# ESP32.net
KiCad netlist of a schematic drawn in Altium Designer
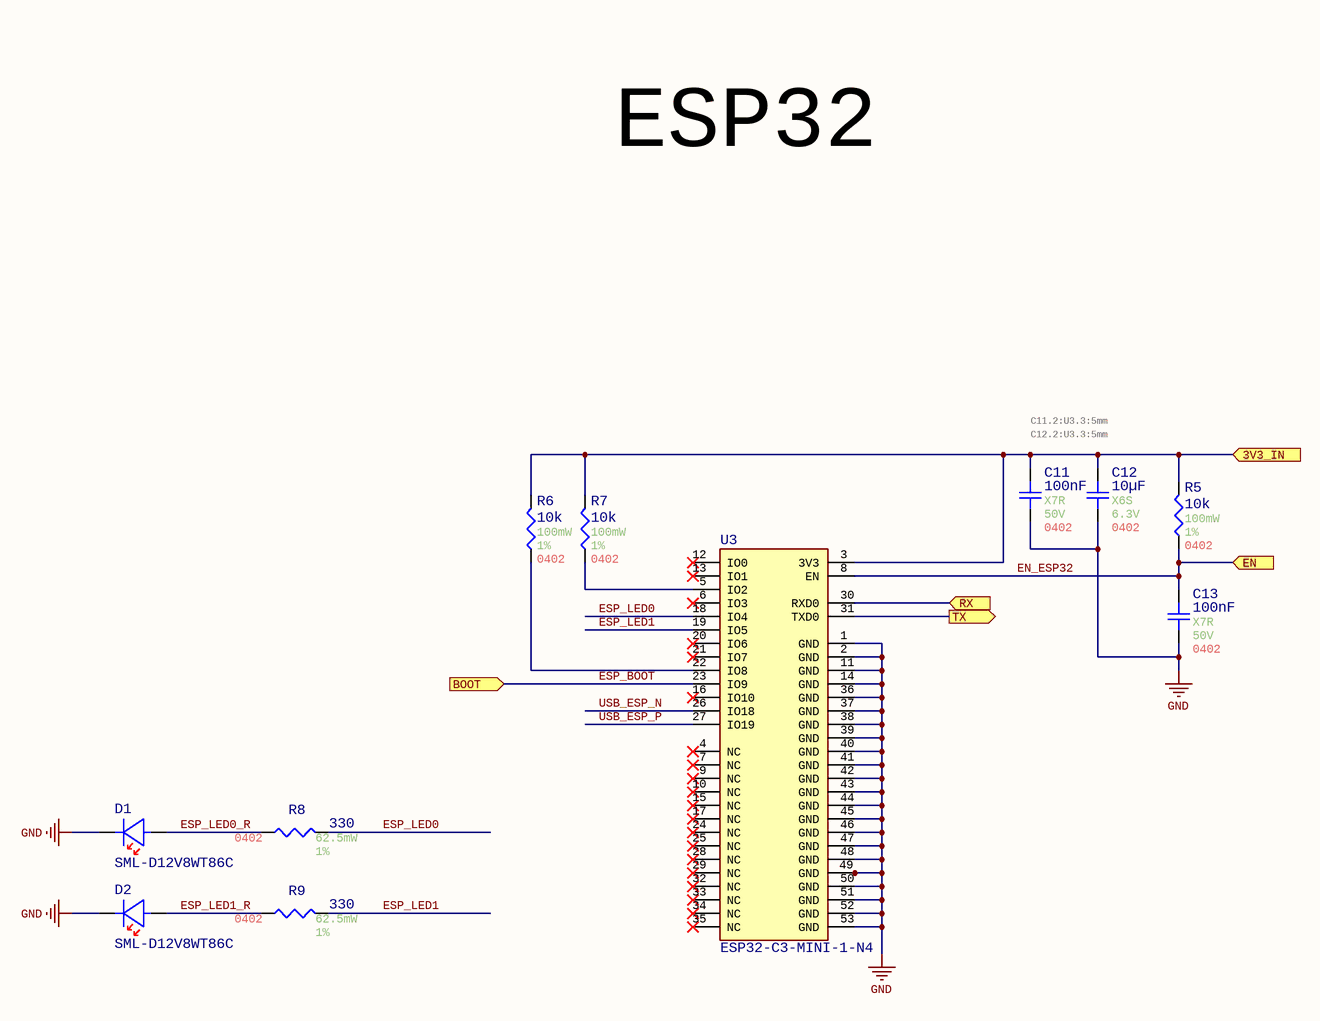
[diagram p0: ESP32.SchDoc]

(export (version "E")
  (design (tool "Eeschema 10.0.6"))
  (components
    (comp (ref "C11")
      (value "100nF")
      (footprint "Generic 0402 capacitor")
      (fields
        (field (name "TEMPERATURE COEFFICIENT") "X7R")
        (field (name "VOLTAGE RATING") "50V")
        (field (name "CASE/PACKAGE") "0402")
        (field (name "TOLERANCE") "10%")
        (field (name "PLACENEAR") "C11.2:U3.3:5mm")
        (field (name "Comment") "GRT155R71H104KE01D")
      )
      (libsource (lib "Raise Robotics") (part "Unpolarized Capacitor"))
    )
    (comp (ref "C12")
      (value "10µF")
      (footprint "Generic 0402 capacitor")
      (description "Multilayer Ceramic Capacitors MLCC - SMD/SMT 0402 10uF 6.3VDC 20% X6S AEC-Q200")
      (fields
        (field (name "TEMPERATURE COEFFICIENT") "X6S")
        (field (name "VOLTAGE RATING") "6.3V")
        (field (name "CASE/PACKAGE") "0402")
        (field (name "TOLERANCE") "20%")
        (field (name "PLACENEAR") "C12.2:U3.3:5mm")
        (field (name "Comment") "GRT155C80J106ME13J")
      )
      (libsource (lib "Raise Robotics") (part "Unpolarized Capacitor"))
    )
    (comp (ref "C13")
      (value "100nF")
      (footprint "Generic 0402 capacitor")
      (fields
        (field (name "TEMPERATURE COEFFICIENT") "X7R")
        (field (name "VOLTAGE RATING") "50V")
        (field (name "CASE/PACKAGE") "0402")
        (field (name "TOLERANCE") "10%")
        (field (name "Comment") "GRT155R71H104KE01D")
      )
      (libsource (lib "Raise Robotics") (part "Unpolarized Capacitor"))
    )
    (comp (ref "D1")
      (value "SML-D12V8WT86C")
      (footprint "FP-SML-D12-MFG")
      (description "Red 630nm LED Indication - Discrete 2.2V 0603 (1608 Metric)")
      (libsource (lib "Raise Robotics") (part "LED Red"))
    )
    (comp (ref "D2")
      (value "SML-D12V8WT86C")
      (footprint "FP-SML-D12-MFG")
      (description "Red 630nm LED Indication - Discrete 2.2V 0603 (1608 Metric)")
      (libsource (lib "Raise Robotics") (part "LED Red"))
    )
    (comp (ref "R5")
      (value "10k")
      (footprint "Generic 0402 Resistor")
      (description "Fixed Resistor, Thin Film, 0.1W, 10000ohm, 50V, 1% +/-Tol, 100ppm/Cel, Surface Mount, 0402")
      (fields
        (field (name "POWER") "100mW")
        (field (name "TOLERANCE") "1%")
        (field (name "CASE/PACKAGE") "0402")
        (field (name "MANUFACTURER PART NUMBER") "Blank")
        (field (name "Comment") "RNCP0402FTD10K0")
      )
      (libsource (lib "Raise Robotics") (part "Resistor"))
    )
    (comp (ref "R6")
      (value "10k")
      (footprint "Generic 0402 Resistor")
      (description "Fixed Resistor, Thin Film, 0.1W, 10000ohm, 50V, 1% +/-Tol, 100ppm/Cel, Surface Mount, 0402")
      (fields
        (field (name "POWER") "100mW")
        (field (name "TOLERANCE") "1%")
        (field (name "CASE/PACKAGE") "0402")
        (field (name "MANUFACTURER PART NUMBER") "Blank")
        (field (name "Comment") "RNCP0402FTD10K0")
      )
      (libsource (lib "Raise Robotics") (part "Resistor"))
    )
    (comp (ref "R7")
      (value "10k")
      (footprint "Generic 0402 Resistor")
      (description "Fixed Resistor, Thin Film, 0.1W, 10000ohm, 50V, 1% +/-Tol, 100ppm/Cel, Surface Mount, 0402")
      (fields
        (field (name "POWER") "100mW")
        (field (name "TOLERANCE") "1%")
        (field (name "CASE/PACKAGE") "0402")
        (field (name "MANUFACTURER PART NUMBER") "Blank")
        (field (name "Comment") "RNCP0402FTD10K0")
      )
      (libsource (lib "Raise Robotics") (part "Resistor"))
    )
    (comp (ref "R8")
      (value "330")
      (footprint "Generic 0402 Resistor")
      (description "Res Thick Film 0402 330 Ohm 1% 0.063W ±100ppm/°C Molded SMD Paper T/R")
      (fields
        (field (name "POWER") "62.5mW")
        (field (name "TOLERANCE") "1%")
        (field (name "CASE/PACKAGE") "0402")
        (field (name "Comment") "RMCF0402FT330R")
      )
      (libsource (lib "Raise Robotics") (part "Resistor"))
    )
    (comp (ref "R9")
      (value "330")
      (footprint "Generic 0402 Resistor")
      (description "Res Thick Film 0402 330 Ohm 1% 0.063W ±100ppm/°C Molded SMD Paper T/R")
      (fields
        (field (name "POWER") "62.5mW")
        (field (name "TOLERANCE") "1%")
        (field (name "CASE/PACKAGE") "0402")
        (field (name "Comment") "RMCF0402FT330R")
      )
      (libsource (lib "Raise Robotics") (part "Resistor"))
    )
    (comp (ref "U3")
      (value "ESP32-C3-MINI-1-N4")
      (footprint "ESP32-C3-MINI-1-N4")
      (libsource (lib "Raise Robotics") (part "ESP32-C3-MINI-1"))
    )
  )
  (nets
    (net (code "1") (name "/3V3_IN") (class "Default")
      (node (ref "C11") (pin "2") (pinfunction "2_2") (pintype "passive"))
      (node (ref "C12") (pin "2") (pinfunction "2_2") (pintype "passive"))
      (node (ref "R5") (pin "2") (pinfunction "2_2") (pintype "passive"))
      (node (ref "R6") (pin "2") (pinfunction "2_2") (pintype "passive"))
      (node (ref "R7") (pin "2") (pinfunction "2_2") (pintype "passive"))
      (node (ref "U3") (pin "3") (pinfunction "3V3_3") (pintype "passive"))
    )
    (net (code "2") (name "/EN_ESP32") (class "Default")
      (node (ref "C13") (pin "2") (pinfunction "2_2") (pintype "passive"))
      (node (ref "R5") (pin "1") (pinfunction "1_1") (pintype "passive"))
      (node (ref "U3") (pin "8") (pinfunction "EN_8") (pintype "passive"))
    )
    (net (code "3") (name "/ESP_BOOT") (class "Default")
      (node (ref "U3") (pin "23") (pinfunction "IO9_23") (pintype "passive"))
    )
    (net (code "4") (name "/ESP_LED0") (class "Default")
      (node (ref "R8") (pin "2") (pinfunction "2_2") (pintype "passive"))
      (node (ref "U3") (pin "18") (pinfunction "IO4_18") (pintype "passive"))
    )
    (net (code "5") (name "/ESP_LED0_R") (class "Default")
      (node (ref "D1") (pin "2") (pinfunction "A_2") (pintype "passive"))
      (node (ref "R8") (pin "1") (pinfunction "1_1") (pintype "passive"))
    )
    (net (code "6") (name "/ESP_LED1") (class "Default")
      (node (ref "R9") (pin "2") (pinfunction "2_2") (pintype "passive"))
      (node (ref "U3") (pin "19") (pinfunction "IO5_19") (pintype "passive"))
    )
    (net (code "7") (name "/ESP_LED1_R") (class "Default")
      (node (ref "D2") (pin "2") (pinfunction "A_2") (pintype "passive"))
      (node (ref "R9") (pin "1") (pinfunction "1_1") (pintype "passive"))
    )
    (net (code "8") (name "/RX") (class "Default")
      (node (ref "U3") (pin "30") (pinfunction "RXD0_30") (pintype "passive"))
    )
    (net (code "9") (name "/TX") (class "Default")
      (node (ref "U3") (pin "31") (pinfunction "TXD0_31") (pintype "passive"))
    )
    (net (code "10") (name "/USB_ESP_N") (class "Default")
      (node (ref "U3") (pin "26") (pinfunction "IO18_26") (pintype "passive"))
    )
    (net (code "11") (name "/USB_ESP_P") (class "Default")
      (node (ref "U3") (pin "27") (pinfunction "IO19_27") (pintype "passive"))
    )
    (net (code "12") (name "GND") (class "Default")
      (node (ref "C11") (pin "1") (pinfunction "1_1") (pintype "passive"))
      (node (ref "C12") (pin "1") (pinfunction "1_1") (pintype "passive"))
      (node (ref "C13") (pin "1") (pinfunction "1_1") (pintype "passive"))
      (node (ref "D1") (pin "1") (pinfunction "C_1") (pintype "passive"))
      (node (ref "D2") (pin "1") (pinfunction "C_1") (pintype "passive"))
      (node (ref "U3") (pin "1") (pinfunction "GND_1") (pintype "passive"))
      (node (ref "U3") (pin "11") (pinfunction "GND_11") (pintype "passive"))
      (node (ref "U3") (pin "14") (pinfunction "GND_14") (pintype "passive"))
      (node (ref "U3") (pin "2") (pinfunction "GND_2") (pintype "passive"))
      (node (ref "U3") (pin "36") (pinfunction "GND_36") (pintype "passive"))
      (node (ref "U3") (pin "37") (pinfunction "GND_37") (pintype "passive"))
      (node (ref "U3") (pin "38") (pinfunction "GND_38") (pintype "passive"))
      (node (ref "U3") (pin "39") (pinfunction "GND_39") (pintype "passive"))
      (node (ref "U3") (pin "40") (pinfunction "GND_40") (pintype "passive"))
      (node (ref "U3") (pin "41") (pinfunction "GND_41") (pintype "passive"))
      (node (ref "U3") (pin "42") (pinfunction "GND_42") (pintype "passive"))
      (node (ref "U3") (pin "43") (pinfunction "GND_43") (pintype "passive"))
      (node (ref "U3") (pin "44") (pinfunction "GND_44") (pintype "passive"))
      (node (ref "U3") (pin "45") (pinfunction "GND_45") (pintype "passive"))
      (node (ref "U3") (pin "46") (pinfunction "GND_46") (pintype "passive"))
      (node (ref "U3") (pin "47") (pinfunction "GND_47") (pintype "passive"))
      (node (ref "U3") (pin "48") (pinfunction "GND_48") (pintype "passive"))
      (node (ref "U3") (pin "49_1") (pinfunction "GND_49_1") (pintype "passive"))
      (node (ref "U3") (pin "49_2") (pinfunction "GND_49_2") (pintype "passive"))
      (node (ref "U3") (pin "49_3") (pinfunction "GND_49_3") (pintype "passive"))
      (node (ref "U3") (pin "49_4") (pinfunction "GND_49_4") (pintype "passive"))
      (node (ref "U3") (pin "49_5") (pinfunction "GND_49_5") (pintype "passive"))
      (node (ref "U3") (pin "49_6") (pinfunction "GND_49_6") (pintype "passive"))
      (node (ref "U3") (pin "49_7") (pinfunction "GND_49_7") (pintype "passive"))
      (node (ref "U3") (pin "49_8") (pinfunction "GND_49_8") (pintype "passive"))
      (node (ref "U3") (pin "49_9") (pinfunction "GND_49_9") (pintype "passive"))
      (node (ref "U3") (pin "50") (pinfunction "GND_50") (pintype "passive"))
      (node (ref "U3") (pin "51") (pinfunction "GND_51") (pintype "passive"))
      (node (ref "U3") (pin "52") (pinfunction "GND_52") (pintype "passive"))
      (node (ref "U3") (pin "53") (pinfunction "GND_53") (pintype "passive"))
    )
    (net (code "13") (name "Net-(U3-IO2)") (class "Default")
      (node (ref "R7") (pin "1") (pinfunction "1_1") (pintype "passive"))
      (node (ref "U3") (pin "5") (pinfunction "IO2_5") (pintype "passive"))
    )
    (net (code "14") (name "Net-(U3-IO8)") (class "Default")
      (node (ref "R6") (pin "1") (pinfunction "1_1") (pintype "passive"))
      (node (ref "U3") (pin "22") (pinfunction "IO8_22") (pintype "passive"))
    )
    (net (code "15") (name "unconnected-(U3-IO0-Pad12)") (class "Default")
      (node (ref "U3") (pin "12") (pinfunction "IO0_12") (pintype "passive+no_connect"))
    )
    (net (code "16") (name "unconnected-(U3-IO1-Pad13)") (class "Default")
      (node (ref "U3") (pin "13") (pinfunction "IO1_13") (pintype "passive+no_connect"))
    )
    (net (code "17") (name "unconnected-(U3-IO3-Pad6)") (class "Default")
      (node (ref "U3") (pin "6") (pinfunction "IO3_6") (pintype "passive+no_connect"))
    )
    (net (code "18") (name "unconnected-(U3-IO6-Pad20)") (class "Default")
      (node (ref "U3") (pin "20") (pinfunction "IO6_20") (pintype "passive+no_connect"))
    )
    (net (code "19") (name "unconnected-(U3-IO7-Pad21)") (class "Default")
      (node (ref "U3") (pin "21") (pinfunction "IO7_21") (pintype "passive+no_connect"))
    )
    (net (code "20") (name "unconnected-(U3-IO10-Pad16)") (class "Default")
      (node (ref "U3") (pin "16") (pinfunction "IO10_16") (pintype "passive+no_connect"))
    )
    (net (code "21") (name "unconnected-(U3-NC-Pad4)") (class "Default")
      (node (ref "U3") (pin "4") (pinfunction "NC_4") (pintype "passive+no_connect"))
    )
    (net (code "22") (name "unconnected-(U3-NC-Pad7)") (class "Default")
      (node (ref "U3") (pin "7") (pinfunction "NC_7") (pintype "passive+no_connect"))
    )
    (net (code "23") (name "unconnected-(U3-NC-Pad9)") (class "Default")
      (node (ref "U3") (pin "9") (pinfunction "NC_9") (pintype "passive+no_connect"))
    )
    (net (code "24") (name "unconnected-(U3-NC-Pad10)") (class "Default")
      (node (ref "U3") (pin "10") (pinfunction "NC_10") (pintype "passive+no_connect"))
    )
    (net (code "25") (name "unconnected-(U3-NC-Pad15)") (class "Default")
      (node (ref "U3") (pin "15") (pinfunction "NC_15") (pintype "passive+no_connect"))
    )
    (net (code "26") (name "unconnected-(U3-NC-Pad17)") (class "Default")
      (node (ref "U3") (pin "17") (pinfunction "NC_17") (pintype "passive+no_connect"))
    )
    (net (code "27") (name "unconnected-(U3-NC-Pad24)") (class "Default")
      (node (ref "U3") (pin "24") (pinfunction "NC_24") (pintype "passive+no_connect"))
    )
    (net (code "28") (name "unconnected-(U3-NC-Pad25)") (class "Default")
      (node (ref "U3") (pin "25") (pinfunction "NC_25") (pintype "passive+no_connect"))
    )
    (net (code "29") (name "unconnected-(U3-NC-Pad28)") (class "Default")
      (node (ref "U3") (pin "28") (pinfunction "NC_28") (pintype "passive+no_connect"))
    )
    (net (code "30") (name "unconnected-(U3-NC-Pad29)") (class "Default")
      (node (ref "U3") (pin "29") (pinfunction "NC_29") (pintype "passive+no_connect"))
    )
    (net (code "31") (name "unconnected-(U3-NC-Pad32)") (class "Default")
      (node (ref "U3") (pin "32") (pinfunction "NC_32") (pintype "passive+no_connect"))
    )
    (net (code "32") (name "unconnected-(U3-NC-Pad33)") (class "Default")
      (node (ref "U3") (pin "33") (pinfunction "NC_33") (pintype "passive+no_connect"))
    )
    (net (code "33") (name "unconnected-(U3-NC-Pad34)") (class "Default")
      (node (ref "U3") (pin "34") (pinfunction "NC_34") (pintype "passive+no_connect"))
    )
    (net (code "34") (name "unconnected-(U3-NC-Pad35)") (class "Default")
      (node (ref "U3") (pin "35") (pinfunction "NC_35") (pintype "passive+no_connect"))
    )
  )
)
